# 07-FPGA.net
KiCad netlist of a schematic drawn in Altium Designer
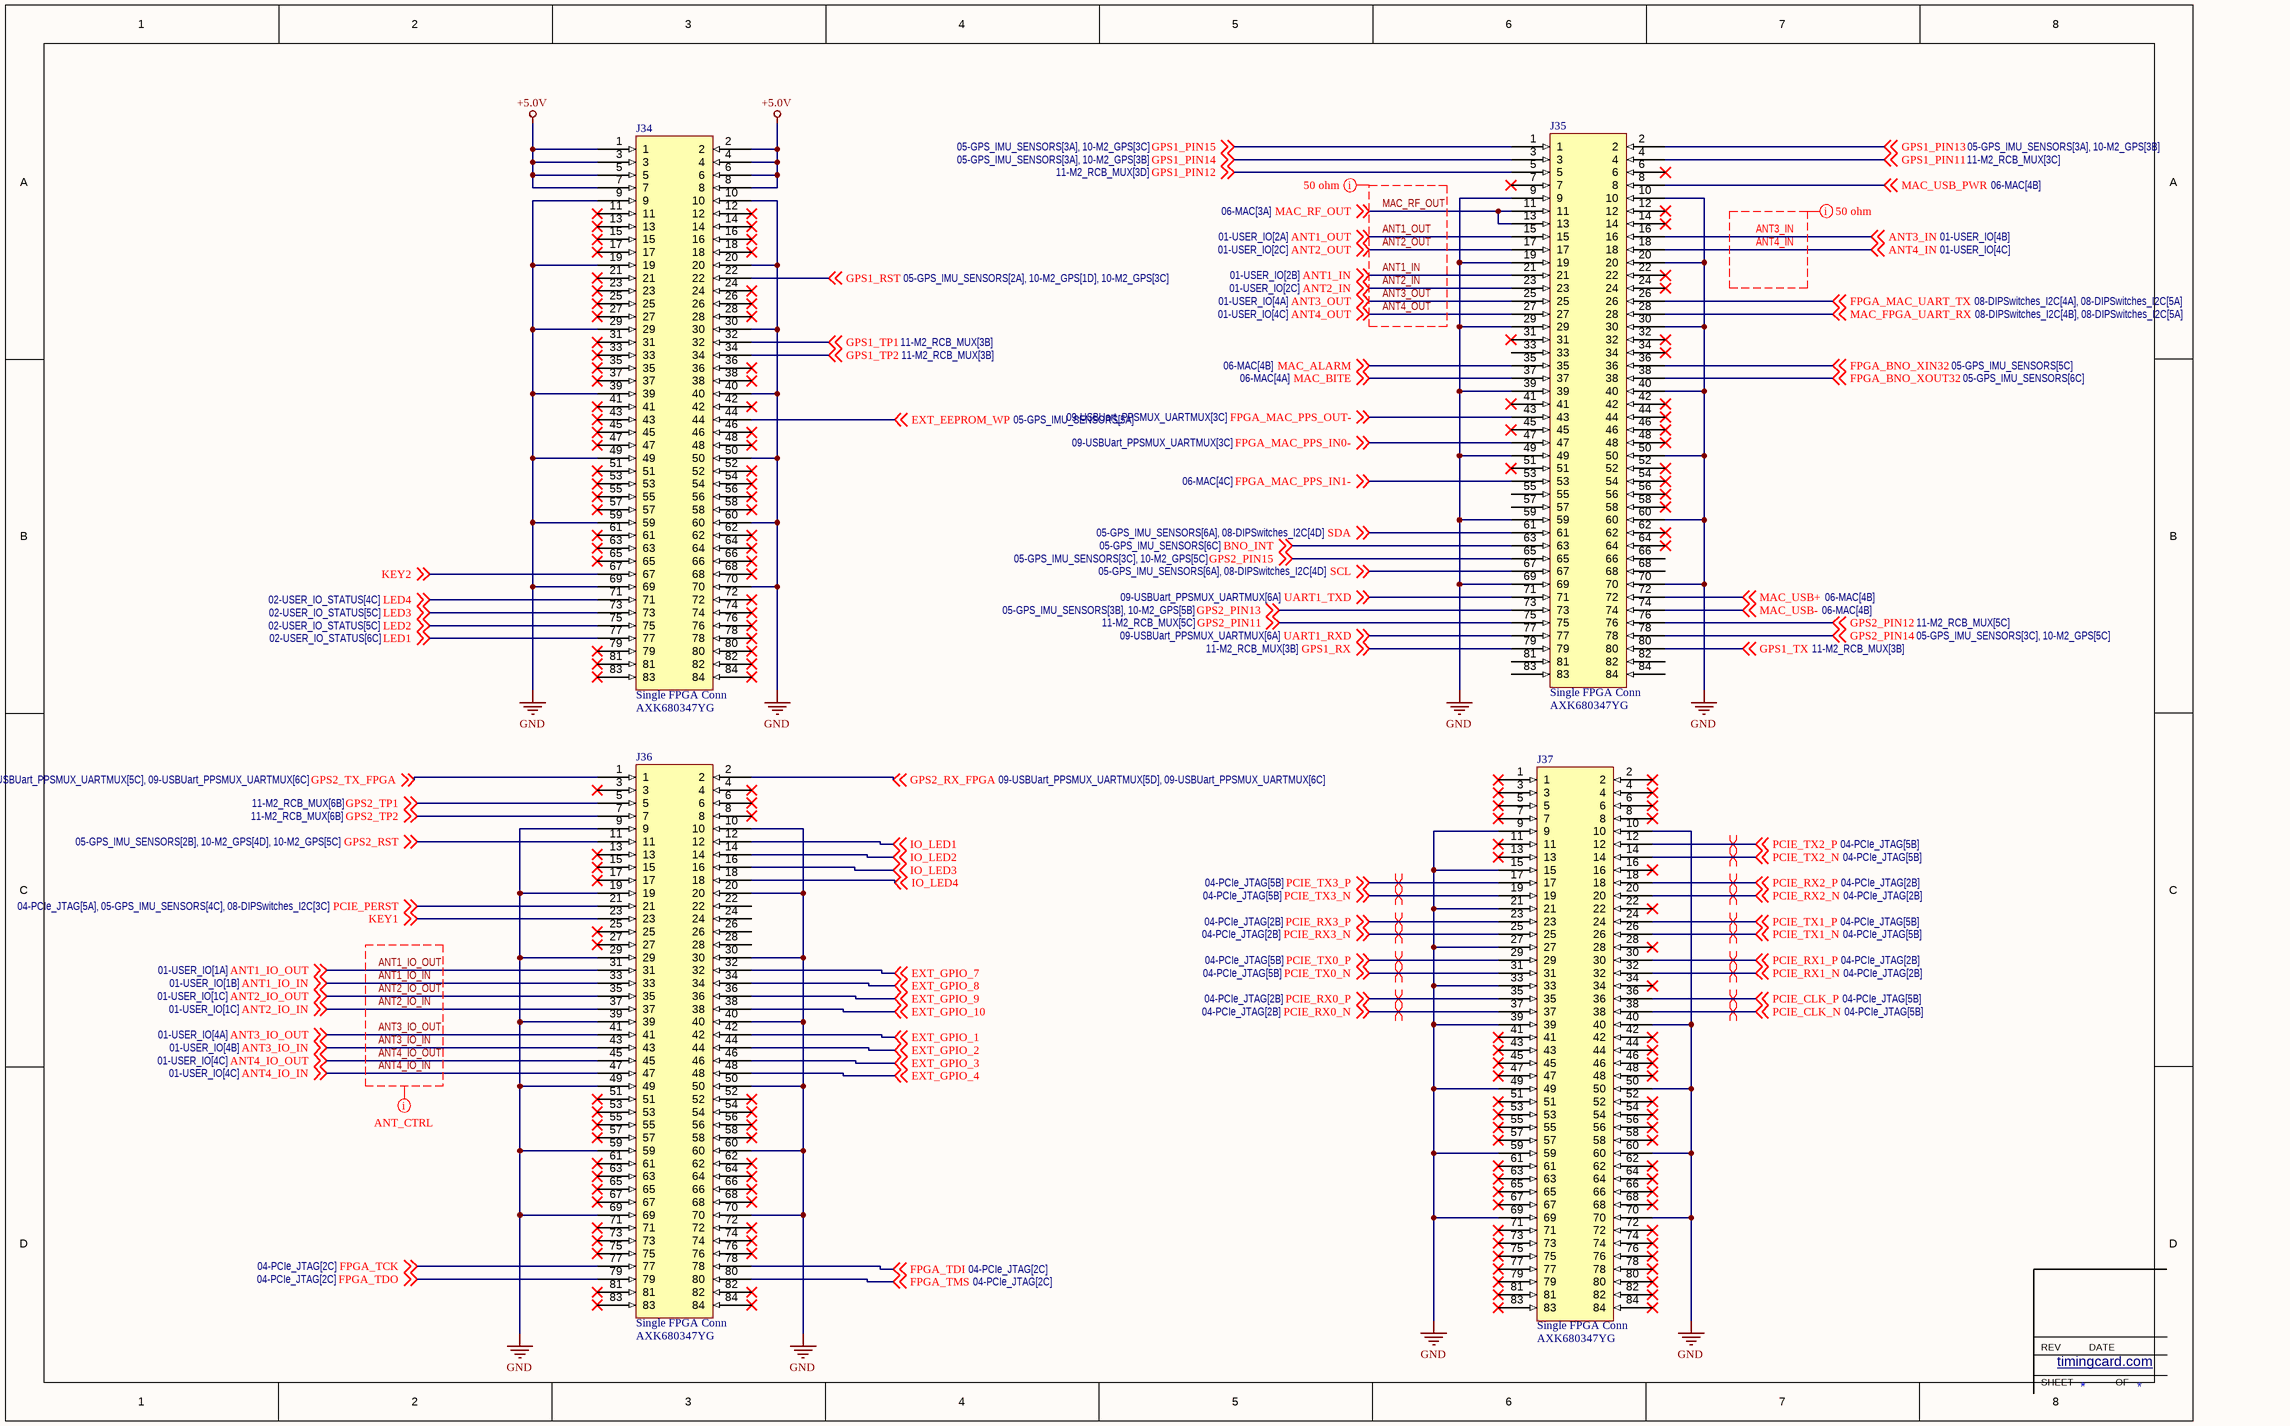
[diagram p0: 07-FPGA.SchDoc]

(export (version "E")
  (design (tool "Eeschema 10.0.6"))
  (components
    (comp (ref "J34")
      (value "Single FPGA Conn")
      (footprint "SingleFPGAConn")
      (description "AXK680347YG")
      (fields (field (name "PART NUMBER") "AXK680347YG"))
      (libsource (lib "FPGA_CONN") (part "Single FPGA Conn"))
    )
    (comp (ref "J35")
      (value "Single FPGA Conn")
      (footprint "SingleFPGAConn")
      (description "AXK680347YG")
      (fields (field (name "PART NUMBER") "AXK680347YG"))
      (libsource (lib "FPGA_CONN") (part "Single FPGA Conn"))
    )
    (comp (ref "J36")
      (value "Single FPGA Conn")
      (footprint "SingleFPGAConn")
      (description "AXK680347YG")
      (fields (field (name "PART NUMBER") "AXK680347YG"))
      (libsource (lib "FPGA_CONN") (part "Single FPGA Conn"))
    )
    (comp (ref "J37")
      (value "Single FPGA Conn")
      (footprint "SingleFPGAConn")
      (description "AXK680347YG")
      (fields (field (name "PART NUMBER") "AXK680347YG"))
      (libsource (lib "FPGA_CONN") (part "Single FPGA Conn"))
    )
  )
  (nets
    (net (code "1") (name "+5.0V") (class "Default")
      (node (ref "J34") (pin "1") (pinfunction "1_1") (pintype "input"))
      (node (ref "J34") (pin "2") (pinfunction "2_2") (pintype "input"))
      (node (ref "J34") (pin "3") (pinfunction "3_3") (pintype "input"))
      (node (ref "J34") (pin "4") (pinfunction "4_4") (pintype "input"))
      (node (ref "J34") (pin "5") (pinfunction "5_5") (pintype "input"))
      (node (ref "J34") (pin "6") (pinfunction "6_6") (pintype "input"))
      (node (ref "J34") (pin "7") (pinfunction "7_7") (pintype "input"))
      (node (ref "J34") (pin "8") (pinfunction "8_8") (pintype "input"))
    )
    (net (code "2") (name "ANT1_IN") (class "Default")
      (node (ref "J35") (pin "21") (pinfunction "21_21") (pintype "input"))
    )
    (net (code "3") (name "ANT1_IO_IN") (class "Default")
      (node (ref "J36") (pin "33") (pinfunction "33_33") (pintype "input"))
    )
    (net (code "4") (name "ANT1_IO_OUT") (class "Default")
      (node (ref "J36") (pin "31") (pinfunction "31_31") (pintype "input"))
    )
    (net (code "5") (name "ANT1_OUT") (class "Default")
      (node (ref "J35") (pin "15") (pinfunction "15_15") (pintype "input"))
    )
    (net (code "6") (name "ANT2_IN") (class "Default")
      (node (ref "J35") (pin "23") (pinfunction "23_23") (pintype "input"))
    )
    (net (code "7") (name "ANT2_IO_IN") (class "Default")
      (node (ref "J36") (pin "37") (pinfunction "37_37") (pintype "input"))
    )
    (net (code "8") (name "ANT2_IO_OUT") (class "Default")
      (node (ref "J36") (pin "35") (pinfunction "35_35") (pintype "input"))
    )
    (net (code "9") (name "ANT2_OUT") (class "Default")
      (node (ref "J35") (pin "17") (pinfunction "17_17") (pintype "input"))
    )
    (net (code "10") (name "ANT3_IN") (class "Default")
      (node (ref "J35") (pin "16") (pinfunction "16_16") (pintype "input"))
    )
    (net (code "11") (name "ANT3_IO_IN") (class "Default")
      (node (ref "J36") (pin "43") (pinfunction "43_43") (pintype "input"))
    )
    (net (code "12") (name "ANT3_IO_OUT") (class "Default")
      (node (ref "J36") (pin "41") (pinfunction "41_41") (pintype "input"))
    )
    (net (code "13") (name "ANT3_OUT") (class "Default")
      (node (ref "J35") (pin "25") (pinfunction "25_25") (pintype "input"))
    )
    (net (code "14") (name "ANT4_IN") (class "Default")
      (node (ref "J35") (pin "18") (pinfunction "18_18") (pintype "input"))
    )
    (net (code "15") (name "ANT4_IO_IN") (class "Default")
      (node (ref "J36") (pin "47") (pinfunction "47_47") (pintype "input"))
    )
    (net (code "16") (name "ANT4_IO_OUT") (class "Default")
      (node (ref "J36") (pin "45") (pinfunction "45_45") (pintype "input"))
    )
    (net (code "17") (name "ANT4_OUT") (class "Default")
      (node (ref "J35") (pin "27") (pinfunction "27_27") (pintype "input"))
    )
    (net (code "18") (name "BNO_INT") (class "Default")
      (node (ref "J35") (pin "63") (pinfunction "63_63") (pintype "input"))
    )
    (net (code "19") (name "EXT_EEPROM_WP") (class "Default")
      (node (ref "J34") (pin "44") (pinfunction "44_44") (pintype "input"))
    )
    (net (code "20") (name "EXT_GPIO_1") (class "Default")
      (node (ref "J36") (pin "42") (pinfunction "42_42") (pintype "input"))
    )
    (net (code "21") (name "EXT_GPIO_2") (class "Default")
      (node (ref "J36") (pin "44") (pinfunction "44_44") (pintype "input"))
    )
    (net (code "22") (name "EXT_GPIO_3") (class "Default")
      (node (ref "J36") (pin "46") (pinfunction "46_46") (pintype "input"))
    )
    (net (code "23") (name "EXT_GPIO_4") (class "Default")
      (node (ref "J36") (pin "48") (pinfunction "48_48") (pintype "input"))
    )
    (net (code "24") (name "EXT_GPIO_7") (class "Default")
      (node (ref "J36") (pin "32") (pinfunction "32_32") (pintype "input"))
    )
    (net (code "25") (name "EXT_GPIO_8") (class "Default")
      (node (ref "J36") (pin "34") (pinfunction "34_34") (pintype "input"))
    )
    (net (code "26") (name "EXT_GPIO_9") (class "Default")
      (node (ref "J36") (pin "36") (pinfunction "36_36") (pintype "input"))
    )
    (net (code "27") (name "EXT_GPIO_10") (class "Default")
      (node (ref "J36") (pin "38") (pinfunction "38_38") (pintype "input"))
    )
    (net (code "28") (name "FPGA_BNO_XIN32") (class "Default")
      (node (ref "J35") (pin "36") (pinfunction "36_36") (pintype "input"))
    )
    (net (code "29") (name "FPGA_BNO_XOUT32") (class "Default")
      (node (ref "J35") (pin "38") (pinfunction "38_38") (pintype "input"))
    )
    (net (code "30") (name "FPGA_MAC_PPS_IN0-") (class "Default")
      (node (ref "J35") (pin "47") (pinfunction "47_47") (pintype "input"))
    )
    (net (code "31") (name "FPGA_MAC_PPS_IN1-") (class "Default")
      (node (ref "J35") (pin "53") (pinfunction "53_53") (pintype "input"))
    )
    (net (code "32") (name "FPGA_MAC_PPS_OUT-") (class "Default")
      (node (ref "J35") (pin "43") (pinfunction "43_43") (pintype "input"))
    )
    (net (code "33") (name "FPGA_MAC_UART_TX") (class "Default")
      (node (ref "J35") (pin "26") (pinfunction "26_26") (pintype "input"))
    )
    (net (code "34") (name "FPGA_TCK") (class "Default")
      (node (ref "J36") (pin "77") (pinfunction "77_77") (pintype "input"))
    )
    (net (code "35") (name "FPGA_TDI") (class "Default")
      (node (ref "J36") (pin "78") (pinfunction "78_78") (pintype "input"))
    )
    (net (code "36") (name "FPGA_TDO") (class "Default")
      (node (ref "J36") (pin "79") (pinfunction "79_79") (pintype "input"))
    )
    (net (code "37") (name "FPGA_TMS") (class "Default")
      (node (ref "J36") (pin "80") (pinfunction "80_80") (pintype "input"))
    )
    (net (code "38") (name "GND") (class "Default")
      (node (ref "J34") (pin "10") (pinfunction "10_10") (pintype "input"))
      (node (ref "J34") (pin "19") (pinfunction "19_19") (pintype "input"))
      (node (ref "J34") (pin "20") (pinfunction "20_20") (pintype "input"))
      (node (ref "J34") (pin "29") (pinfunction "29_29") (pintype "input"))
      (node (ref "J34") (pin "30") (pinfunction "30_30") (pintype "input"))
      (node (ref "J34") (pin "39") (pinfunction "39_39") (pintype "input"))
      (node (ref "J34") (pin "40") (pinfunction "40_40") (pintype "input"))
      (node (ref "J34") (pin "49") (pinfunction "49_49") (pintype "input"))
      (node (ref "J34") (pin "50") (pinfunction "50_50") (pintype "input"))
      (node (ref "J34") (pin "59") (pinfunction "59_59") (pintype "input"))
      (node (ref "J34") (pin "60") (pinfunction "60_60") (pintype "input"))
      (node (ref "J34") (pin "69") (pinfunction "69_69") (pintype "input"))
      (node (ref "J34") (pin "70") (pinfunction "70_70") (pintype "input"))
      (node (ref "J34") (pin "9") (pinfunction "9_9") (pintype "input"))
      (node (ref "J35") (pin "10") (pinfunction "10_10") (pintype "input"))
      (node (ref "J35") (pin "19") (pinfunction "19_19") (pintype "input"))
      (node (ref "J35") (pin "20") (pinfunction "20_20") (pintype "input"))
      (node (ref "J35") (pin "29") (pinfunction "29_29") (pintype "input"))
      (node (ref "J35") (pin "30") (pinfunction "30_30") (pintype "input"))
      (node (ref "J35") (pin "39") (pinfunction "39_39") (pintype "input"))
      (node (ref "J35") (pin "40") (pinfunction "40_40") (pintype "input"))
      (node (ref "J35") (pin "49") (pinfunction "49_49") (pintype "input"))
      (node (ref "J35") (pin "50") (pinfunction "50_50") (pintype "input"))
      (node (ref "J35") (pin "59") (pinfunction "59_59") (pintype "input"))
      (node (ref "J35") (pin "60") (pinfunction "60_60") (pintype "input"))
      (node (ref "J35") (pin "69") (pinfunction "69_69") (pintype "input"))
      (node (ref "J35") (pin "70") (pinfunction "70_70") (pintype "input"))
      (node (ref "J35") (pin "9") (pinfunction "9_9") (pintype "input"))
      (node (ref "J36") (pin "10") (pinfunction "10_10") (pintype "input"))
      (node (ref "J36") (pin "19") (pinfunction "19_19") (pintype "input"))
      (node (ref "J36") (pin "20") (pinfunction "20_20") (pintype "input"))
      (node (ref "J36") (pin "29") (pinfunction "29_29") (pintype "input"))
      (node (ref "J36") (pin "30") (pinfunction "30_30") (pintype "input"))
      (node (ref "J36") (pin "39") (pinfunction "39_39") (pintype "input"))
      (node (ref "J36") (pin "40") (pinfunction "40_40") (pintype "input"))
      (node (ref "J36") (pin "49") (pinfunction "49_49") (pintype "input"))
      (node (ref "J36") (pin "50") (pinfunction "50_50") (pintype "input"))
      (node (ref "J36") (pin "59") (pinfunction "59_59") (pintype "input"))
      (node (ref "J36") (pin "60") (pinfunction "60_60") (pintype "input"))
      (node (ref "J36") (pin "69") (pinfunction "69_69") (pintype "input"))
      (node (ref "J36") (pin "70") (pinfunction "70_70") (pintype "input"))
      (node (ref "J36") (pin "9") (pinfunction "9_9") (pintype "input"))
      (node (ref "J37") (pin "10") (pinfunction "10_10") (pintype "input"))
      (node (ref "J37") (pin "15") (pinfunction "15_15") (pintype "input"))
      (node (ref "J37") (pin "21") (pinfunction "21_21") (pintype "input"))
      (node (ref "J37") (pin "27") (pinfunction "27_27") (pintype "input"))
      (node (ref "J37") (pin "33") (pinfunction "33_33") (pintype "input"))
      (node (ref "J37") (pin "39") (pinfunction "39_39") (pintype "input"))
      (node (ref "J37") (pin "40") (pinfunction "40_40") (pintype "input"))
      (node (ref "J37") (pin "49") (pinfunction "49_49") (pintype "input"))
      (node (ref "J37") (pin "50") (pinfunction "50_50") (pintype "input"))
      (node (ref "J37") (pin "59") (pinfunction "59_59") (pintype "input"))
      (node (ref "J37") (pin "60") (pinfunction "60_60") (pintype "input"))
      (node (ref "J37") (pin "69") (pinfunction "69_69") (pintype "input"))
      (node (ref "J37") (pin "70") (pinfunction "70_70") (pintype "input"))
      (node (ref "J37") (pin "9") (pinfunction "9_9") (pintype "input"))
    )
    (net (code "39") (name "GPS1_PIN11") (class "Default")
      (node (ref "J35") (pin "4") (pinfunction "4_4") (pintype "input"))
    )
    (net (code "40") (name "GPS1_PIN12") (class "Default")
      (node (ref "J35") (pin "5") (pinfunction "5_5") (pintype "input"))
    )
    (net (code "41") (name "GPS1_PIN13") (class "Default")
      (node (ref "J35") (pin "2") (pinfunction "2_2") (pintype "input"))
    )
    (net (code "42") (name "GPS1_PIN14") (class "Default")
      (node (ref "J35") (pin "3") (pinfunction "3_3") (pintype "input"))
    )
    (net (code "43") (name "GPS1_PIN15") (class "Default")
      (node (ref "J35") (pin "1") (pinfunction "1_1") (pintype "input"))
    )
    (net (code "44") (name "GPS1_RST") (class "Default")
      (node (ref "J34") (pin "22") (pinfunction "22_22") (pintype "input"))
    )
    (net (code "45") (name "GPS1_RX") (class "Default")
      (node (ref "J35") (pin "79") (pinfunction "79_79") (pintype "input"))
    )
    (net (code "46") (name "GPS1_TP1") (class "Default")
      (node (ref "J34") (pin "32") (pinfunction "32_32") (pintype "input"))
    )
    (net (code "47") (name "GPS1_TP2") (class "Default")
      (node (ref "J34") (pin "34") (pinfunction "34_34") (pintype "input"))
    )
    (net (code "48") (name "GPS1_TX") (class "Default")
      (node (ref "J35") (pin "80") (pinfunction "80_80") (pintype "input"))
    )
    (net (code "49") (name "GPS2_PIN11") (class "Default")
      (node (ref "J35") (pin "75") (pinfunction "75_75") (pintype "input"))
    )
    (net (code "50") (name "GPS2_PIN12") (class "Default")
      (node (ref "J35") (pin "76") (pinfunction "76_76") (pintype "input"))
    )
    (net (code "51") (name "GPS2_PIN13") (class "Default")
      (node (ref "J35") (pin "73") (pinfunction "73_73") (pintype "input"))
    )
    (net (code "52") (name "GPS2_PIN14") (class "Default")
      (node (ref "J35") (pin "78") (pinfunction "78_78") (pintype "input"))
    )
    (net (code "53") (name "GPS2_PIN15") (class "Default")
      (node (ref "J35") (pin "65") (pinfunction "65_65") (pintype "input"))
    )
    (net (code "54") (name "GPS2_RST") (class "Default")
      (node (ref "J36") (pin "11") (pinfunction "11_11") (pintype "input"))
    )
    (net (code "55") (name "GPS2_RX_FPGA") (class "Default")
      (node (ref "J36") (pin "2") (pinfunction "2_2") (pintype "input"))
    )
    (net (code "56") (name "GPS2_TP1") (class "Default")
      (node (ref "J36") (pin "5") (pinfunction "5_5") (pintype "input"))
    )
    (net (code "57") (name "GPS2_TP2") (class "Default")
      (node (ref "J36") (pin "7") (pinfunction "7_7") (pintype "input"))
    )
    (net (code "58") (name "GPS2_TX_FPGA") (class "Default")
      (node (ref "J36") (pin "1") (pinfunction "1_1") (pintype "input"))
    )
    (net (code "59") (name "IO_LED1") (class "Default")
      (node (ref "J36") (pin "12") (pinfunction "12_12") (pintype "input"))
    )
    (net (code "60") (name "IO_LED2") (class "Default")
      (node (ref "J36") (pin "14") (pinfunction "14_14") (pintype "input"))
    )
    (net (code "61") (name "IO_LED3") (class "Default")
      (node (ref "J36") (pin "16") (pinfunction "16_16") (pintype "input"))
    )
    (net (code "62") (name "IO_LED4") (class "Default")
      (node (ref "J36") (pin "18") (pinfunction "18_18") (pintype "input"))
    )
    (net (code "63") (name "KEY1") (class "Default")
      (node (ref "J36") (pin "23") (pinfunction "23_23") (pintype "input"))
    )
    (net (code "64") (name "KEY2") (class "Default")
      (node (ref "J34") (pin "67") (pinfunction "67_67") (pintype "input"))
    )
    (net (code "65") (name "LED1") (class "Default")
      (node (ref "J34") (pin "77") (pinfunction "77_77") (pintype "input"))
    )
    (net (code "66") (name "LED2") (class "Default")
      (node (ref "J34") (pin "75") (pinfunction "75_75") (pintype "input"))
    )
    (net (code "67") (name "LED3") (class "Default")
      (node (ref "J34") (pin "73") (pinfunction "73_73") (pintype "input"))
    )
    (net (code "68") (name "LED4") (class "Default")
      (node (ref "J34") (pin "71") (pinfunction "71_71") (pintype "input"))
    )
    (net (code "69") (name "MAC_ALARM") (class "Default")
      (node (ref "J35") (pin "35") (pinfunction "35_35") (pintype "input"))
    )
    (net (code "70") (name "MAC_BITE") (class "Default")
      (node (ref "J35") (pin "37") (pinfunction "37_37") (pintype "input"))
    )
    (net (code "71") (name "MAC_FPGA_UART_RX") (class "Default")
      (node (ref "J35") (pin "28") (pinfunction "28_28") (pintype "input"))
    )
    (net (code "72") (name "MAC_RF_OUT") (class "Default")
      (node (ref "J35") (pin "11") (pinfunction "11_11") (pintype "input"))
      (node (ref "J35") (pin "13") (pinfunction "13_13") (pintype "input"))
    )
    (net (code "73") (name "MAC_USB+") (class "Default")
      (node (ref "J35") (pin "72") (pinfunction "72_72") (pintype "input"))
    )
    (net (code "74") (name "MAC_USB-") (class "Default")
      (node (ref "J35") (pin "74") (pinfunction "74_74") (pintype "input"))
    )
    (net (code "75") (name "MAC_USB_PWR") (class "Default")
      (node (ref "J35") (pin "8") (pinfunction "8_8") (pintype "input"))
    )
    (net (code "76") (name "PCIE_CLK_N") (class "Default")
      (node (ref "J37") (pin "38") (pinfunction "38_38") (pintype "input"))
    )
    (net (code "77") (name "PCIE_CLK_P") (class "Default")
      (node (ref "J37") (pin "36") (pinfunction "36_36") (pintype "input"))
    )
    (net (code "78") (name "PCIE_PERST") (class "Default")
      (node (ref "J36") (pin "21") (pinfunction "21_21") (pintype "input"))
    )
    (net (code "79") (name "PCIE_RX0_N") (class "Default")
      (node (ref "J37") (pin "37") (pinfunction "37_37") (pintype "input"))
    )
    (net (code "80") (name "PCIE_RX0_P") (class "Default")
      (node (ref "J37") (pin "35") (pinfunction "35_35") (pintype "input"))
    )
    (net (code "81") (name "PCIE_RX1_N") (class "Default")
      (node (ref "J37") (pin "32") (pinfunction "32_32") (pintype "input"))
    )
    (net (code "82") (name "PCIE_RX1_P") (class "Default")
      (node (ref "J37") (pin "30") (pinfunction "30_30") (pintype "input"))
    )
    (net (code "83") (name "PCIE_RX2_N") (class "Default")
      (node (ref "J37") (pin "20") (pinfunction "20_20") (pintype "input"))
    )
    (net (code "84") (name "PCIE_RX2_P") (class "Default")
      (node (ref "J37") (pin "18") (pinfunction "18_18") (pintype "input"))
    )
    (net (code "85") (name "PCIE_RX3_N") (class "Default")
      (node (ref "J37") (pin "25") (pinfunction "25_25") (pintype "input"))
    )
    (net (code "86") (name "PCIE_RX3_P") (class "Default")
      (node (ref "J37") (pin "23") (pinfunction "23_23") (pintype "input"))
    )
    (net (code "87") (name "PCIE_TX0_N") (class "Default")
      (node (ref "J37") (pin "31") (pinfunction "31_31") (pintype "input"))
    )
    (net (code "88") (name "PCIE_TX0_P") (class "Default")
      (node (ref "J37") (pin "29") (pinfunction "29_29") (pintype "input"))
    )
    (net (code "89") (name "PCIE_TX1_N") (class "Default")
      (node (ref "J37") (pin "26") (pinfunction "26_26") (pintype "input"))
    )
    (net (code "90") (name "PCIE_TX1_P") (class "Default")
      (node (ref "J37") (pin "24") (pinfunction "24_24") (pintype "input"))
    )
    (net (code "91") (name "PCIE_TX2_N") (class "Default")
      (node (ref "J37") (pin "14") (pinfunction "14_14") (pintype "input"))
    )
    (net (code "92") (name "PCIE_TX2_P") (class "Default")
      (node (ref "J37") (pin "12") (pinfunction "12_12") (pintype "input"))
    )
    (net (code "93") (name "PCIE_TX3_N") (class "Default")
      (node (ref "J37") (pin "19") (pinfunction "19_19") (pintype "input"))
    )
    (net (code "94") (name "PCIE_TX3_P") (class "Default")
      (node (ref "J37") (pin "17") (pinfunction "17_17") (pintype "input"))
    )
    (net (code "95") (name "SCL") (class "Default")
      (node (ref "J35") (pin "67") (pinfunction "67_67") (pintype "input"))
    )
    (net (code "96") (name "SDA") (class "Default")
      (node (ref "J35") (pin "61") (pinfunction "61_61") (pintype "input"))
    )
    (net (code "97") (name "UART1_RXD") (class "Default")
      (node (ref "J35") (pin "77") (pinfunction "77_77") (pintype "input"))
    )
    (net (code "98") (name "UART1_TXD") (class "Default")
      (node (ref "J35") (pin "71") (pinfunction "71_71") (pintype "input"))
    )
    (net (code "99") (name "unconnected-(J34-Pad11)") (class "Default")
      (node (ref "J34") (pin "11") (pinfunction "11_11") (pintype "input+no_connect"))
    )
    (net (code "100") (name "unconnected-(J34-Pad12)") (class "Default")
      (node (ref "J34") (pin "12") (pinfunction "12_12") (pintype "input+no_connect"))
    )
    (net (code "101") (name "unconnected-(J34-Pad13)") (class "Default")
      (node (ref "J34") (pin "13") (pinfunction "13_13") (pintype "input+no_connect"))
    )
    (net (code "102") (name "unconnected-(J34-Pad14)") (class "Default")
      (node (ref "J34") (pin "14") (pinfunction "14_14") (pintype "input+no_connect"))
    )
    (net (code "103") (name "unconnected-(J34-Pad15)") (class "Default")
      (node (ref "J34") (pin "15") (pinfunction "15_15") (pintype "input+no_connect"))
    )
    (net (code "104") (name "unconnected-(J34-Pad16)") (class "Default")
      (node (ref "J34") (pin "16") (pinfunction "16_16") (pintype "input+no_connect"))
    )
    (net (code "105") (name "unconnected-(J34-Pad17)") (class "Default")
      (node (ref "J34") (pin "17") (pinfunction "17_17") (pintype "input+no_connect"))
    )
    (net (code "106") (name "unconnected-(J34-Pad18)") (class "Default")
      (node (ref "J34") (pin "18") (pinfunction "18_18") (pintype "input+no_connect"))
    )
    (net (code "107") (name "unconnected-(J34-Pad21)") (class "Default")
      (node (ref "J34") (pin "21") (pinfunction "21_21") (pintype "input+no_connect"))
    )
    (net (code "108") (name "unconnected-(J34-Pad23)") (class "Default")
      (node (ref "J34") (pin "23") (pinfunction "23_23") (pintype "input+no_connect"))
    )
    (net (code "109") (name "unconnected-(J34-Pad24)") (class "Default")
      (node (ref "J34") (pin "24") (pinfunction "24_24") (pintype "input+no_connect"))
    )
    (net (code "110") (name "unconnected-(J34-Pad25)") (class "Default")
      (node (ref "J34") (pin "25") (pinfunction "25_25") (pintype "input+no_connect"))
    )
    (net (code "111") (name "unconnected-(J34-Pad26)") (class "Default")
      (node (ref "J34") (pin "26") (pinfunction "26_26") (pintype "input+no_connect"))
    )
    (net (code "112") (name "unconnected-(J34-Pad27)") (class "Default")
      (node (ref "J34") (pin "27") (pinfunction "27_27") (pintype "input+no_connect"))
    )
    (net (code "113") (name "unconnected-(J34-Pad28)") (class "Default")
      (node (ref "J34") (pin "28") (pinfunction "28_28") (pintype "input+no_connect"))
    )
    (net (code "114") (name "unconnected-(J34-Pad31)") (class "Default")
      (node (ref "J34") (pin "31") (pinfunction "31_31") (pintype "input+no_connect"))
    )
    (net (code "115") (name "unconnected-(J34-Pad33)") (class "Default")
      (node (ref "J34") (pin "33") (pinfunction "33_33") (pintype "input+no_connect"))
    )
    (net (code "116") (name "unconnected-(J34-Pad35)") (class "Default")
      (node (ref "J34") (pin "35") (pinfunction "35_35") (pintype "input+no_connect"))
    )
    (net (code "117") (name "unconnected-(J34-Pad36)") (class "Default")
      (node (ref "J34") (pin "36") (pinfunction "36_36") (pintype "input+no_connect"))
    )
    (net (code "118") (name "unconnected-(J34-Pad37)") (class "Default")
      (node (ref "J34") (pin "37") (pinfunction "37_37") (pintype "input+no_connect"))
    )
    (net (code "119") (name "unconnected-(J34-Pad38)") (class "Default")
      (node (ref "J34") (pin "38") (pinfunction "38_38") (pintype "input+no_connect"))
    )
    (net (code "120") (name "unconnected-(J34-Pad41)") (class "Default")
      (node (ref "J34") (pin "41") (pinfunction "41_41") (pintype "input+no_connect"))
    )
    (net (code "121") (name "unconnected-(J34-Pad42)") (class "Default")
      (node (ref "J34") (pin "42") (pinfunction "42_42") (pintype "input+no_connect"))
    )
    (net (code "122") (name "unconnected-(J34-Pad43)") (class "Default")
      (node (ref "J34") (pin "43") (pinfunction "43_43") (pintype "input+no_connect"))
    )
    (net (code "123") (name "unconnected-(J34-Pad45)") (class "Default")
      (node (ref "J34") (pin "45") (pinfunction "45_45") (pintype "input+no_connect"))
    )
    (net (code "124") (name "unconnected-(J34-Pad46)") (class "Default")
      (node (ref "J34") (pin "46") (pinfunction "46_46") (pintype "input+no_connect"))
    )
    (net (code "125") (name "unconnected-(J34-Pad47)") (class "Default")
      (node (ref "J34") (pin "47") (pinfunction "47_47") (pintype "input+no_connect"))
    )
    (net (code "126") (name "unconnected-(J34-Pad48)") (class "Default")
      (node (ref "J34") (pin "48") (pinfunction "48_48") (pintype "input+no_connect"))
    )
    (net (code "127") (name "unconnected-(J34-Pad51)") (class "Default")
      (node (ref "J34") (pin "51") (pinfunction "51_51") (pintype "input+no_connect"))
    )
    (net (code "128") (name "unconnected-(J34-Pad52)") (class "Default")
      (node (ref "J34") (pin "52") (pinfunction "52_52") (pintype "input+no_connect"))
    )
    (net (code "129") (name "unconnected-(J34-Pad53)") (class "Default")
      (node (ref "J34") (pin "53") (pinfunction "53_53") (pintype "input+no_connect"))
    )
    (net (code "130") (name "unconnected-(J34-Pad54)") (class "Default")
      (node (ref "J34") (pin "54") (pinfunction "54_54") (pintype "input+no_connect"))
    )
    (net (code "131") (name "unconnected-(J34-Pad55)") (class "Default")
      (node (ref "J34") (pin "55") (pinfunction "55_55") (pintype "input+no_connect"))
    )
    (net (code "132") (name "unconnected-(J34-Pad56)") (class "Default")
      (node (ref "J34") (pin "56") (pinfunction "56_56") (pintype "input+no_connect"))
    )
    (net (code "133") (name "unconnected-(J34-Pad57)") (class "Default")
      (node (ref "J34") (pin "57") (pinfunction "57_57") (pintype "input+no_connect"))
    )
    (net (code "134") (name "unconnected-(J34-Pad58)") (class "Default")
      (node (ref "J34") (pin "58") (pinfunction "58_58") (pintype "input+no_connect"))
    )
    (net (code "135") (name "unconnected-(J34-Pad61)") (class "Default")
      (node (ref "J34") (pin "61") (pinfunction "61_61") (pintype "input+no_connect"))
    )
    (net (code "136") (name "unconnected-(J34-Pad62)") (class "Default")
      (node (ref "J34") (pin "62") (pinfunction "62_62") (pintype "input+no_connect"))
    )
    (net (code "137") (name "unconnected-(J34-Pad63)") (class "Default")
      (node (ref "J34") (pin "63") (pinfunction "63_63") (pintype "input+no_connect"))
    )
    (net (code "138") (name "unconnected-(J34-Pad64)") (class "Default")
      (node (ref "J34") (pin "64") (pinfunction "64_64") (pintype "input+no_connect"))
    )
    (net (code "139") (name "unconnected-(J34-Pad65)") (class "Default")
      (node (ref "J34") (pin "65") (pinfunction "65_65") (pintype "input+no_connect"))
    )
    (net (code "140") (name "unconnected-(J34-Pad66)") (class "Default")
      (node (ref "J34") (pin "66") (pinfunction "66_66") (pintype "input+no_connect"))
    )
    (net (code "141") (name "unconnected-(J34-Pad68)") (class "Default")
      (node (ref "J34") (pin "68") (pinfunction "68_68") (pintype "input+no_connect"))
    )
    (net (code "142") (name "unconnected-(J34-Pad72)") (class "Default")
      (node (ref "J34") (pin "72") (pinfunction "72_72") (pintype "input+no_connect"))
    )
    (net (code "143") (name "unconnected-(J34-Pad74)") (class "Default")
      (node (ref "J34") (pin "74") (pinfunction "74_74") (pintype "input+no_connect"))
    )
    (net (code "144") (name "unconnected-(J34-Pad76)") (class "Default")
      (node (ref "J34") (pin "76") (pinfunction "76_76") (pintype "input+no_connect"))
    )
    (net (code "145") (name "unconnected-(J34-Pad78)") (class "Default")
      (node (ref "J34") (pin "78") (pinfunction "78_78") (pintype "input+no_connect"))
    )
    (net (code "146") (name "unconnected-(J34-Pad79)") (class "Default")
      (node (ref "J34") (pin "79") (pinfunction "79_79") (pintype "input+no_connect"))
    )
    (net (code "147") (name "unconnected-(J34-Pad80)") (class "Default")
      (node (ref "J34") (pin "80") (pinfunction "80_80") (pintype "input+no_connect"))
    )
    (net (code "148") (name "unconnected-(J34-Pad81)") (class "Default")
      (node (ref "J34") (pin "81") (pinfunction "81_81") (pintype "input+no_connect"))
    )
    (net (code "149") (name "unconnected-(J34-Pad82)") (class "Default")
      (node (ref "J34") (pin "82") (pinfunction "82_82") (pintype "input+no_connect"))
    )
    (net (code "150") (name "unconnected-(J34-Pad83)") (class "Default")
      (node (ref "J34") (pin "83") (pinfunction "83_83") (pintype "input+no_connect"))
    )
    (net (code "151") (name "unconnected-(J34-Pad84)") (class "Default")
      (node (ref "J34") (pin "84") (pinfunction "84_84") (pintype "input+no_connect"))
    )
    (net (code "152") (name "unconnected-(J35-Pad6)") (class "Default")
      (node (ref "J35") (pin "6") (pinfunction "6_6") (pintype "input+no_connect"))
    )
    (net (code "153") (name "unconnected-(J35-Pad7)") (class "Default")
      (node (ref "J35") (pin "7") (pinfunction "7_7") (pintype "input+no_connect"))
    )
    (net (code "154") (name "unconnected-(J35-Pad12)") (class "Default")
      (node (ref "J35") (pin "12") (pinfunction "12_12") (pintype "input+no_connect"))
    )
    (net (code "155") (name "unconnected-(J35-Pad14)") (class "Default")
      (node (ref "J35") (pin "14") (pinfunction "14_14") (pintype "input+no_connect"))
    )
    (net (code "156") (name "unconnected-(J35-Pad22)") (class "Default")
      (node (ref "J35") (pin "22") (pinfunction "22_22") (pintype "input+no_connect"))
    )
    (net (code "157") (name "unconnected-(J35-Pad24)") (class "Default")
      (node (ref "J35") (pin "24") (pinfunction "24_24") (pintype "input+no_connect"))
    )
    (net (code "158") (name "unconnected-(J35-Pad31)") (class "Default")
      (node (ref "J35") (pin "31") (pinfunction "31_31") (pintype "input+no_connect"))
    )
    (net (code "159") (name "unconnected-(J35-Pad32)") (class "Default")
      (node (ref "J35") (pin "32") (pinfunction "32_32") (pintype "input+no_connect"))
    )
    (net (code "160") (name "unconnected-(J35-Pad33)") (class "Default")
      (node (ref "J35") (pin "33") (pinfunction "33_33") (pintype "input"))
    )
    (net (code "161") (name "unconnected-(J35-Pad34)") (class "Default")
      (node (ref "J35") (pin "34") (pinfunction "34_34") (pintype "input+no_connect"))
    )
    (net (code "162") (name "unconnected-(J35-Pad41)") (class "Default")
      (node (ref "J35") (pin "41") (pinfunction "41_41") (pintype "input+no_connect"))
    )
    (net (code "163") (name "unconnected-(J35-Pad42)") (class "Default")
      (node (ref "J35") (pin "42") (pinfunction "42_42") (pintype "input+no_connect"))
    )
    (net (code "164") (name "unconnected-(J35-Pad44)") (class "Default")
      (node (ref "J35") (pin "44") (pinfunction "44_44") (pintype "input+no_connect"))
    )
    (net (code "165") (name "unconnected-(J35-Pad45)") (class "Default")
      (node (ref "J35") (pin "45") (pinfunction "45_45") (pintype "input+no_connect"))
    )
    (net (code "166") (name "unconnected-(J35-Pad46)") (class "Default")
      (node (ref "J35") (pin "46") (pinfunction "46_46") (pintype "input+no_connect"))
    )
    (net (code "167") (name "unconnected-(J35-Pad48)") (class "Default")
      (node (ref "J35") (pin "48") (pinfunction "48_48") (pintype "input+no_connect"))
    )
    (net (code "168") (name "unconnected-(J35-Pad51)") (class "Default")
      (node (ref "J35") (pin "51") (pinfunction "51_51") (pintype "input+no_connect"))
    )
    (net (code "169") (name "unconnected-(J35-Pad52)") (class "Default")
      (node (ref "J35") (pin "52") (pinfunction "52_52") (pintype "input+no_connect"))
    )
    (net (code "170") (name "unconnected-(J35-Pad54)") (class "Default")
      (node (ref "J35") (pin "54") (pinfunction "54_54") (pintype "input+no_connect"))
    )
    (net (code "171") (name "unconnected-(J35-Pad55)") (class "Default")
      (node (ref "J35") (pin "55") (pinfunction "55_55") (pintype "input"))
    )
    (net (code "172") (name "unconnected-(J35-Pad56)") (class "Default")
      (node (ref "J35") (pin "56") (pinfunction "56_56") (pintype "input+no_connect"))
    )
    (net (code "173") (name "unconnected-(J35-Pad57)") (class "Default")
      (node (ref "J35") (pin "57") (pinfunction "57_57") (pintype "input"))
    )
    (net (code "174") (name "unconnected-(J35-Pad58)") (class "Default")
      (node (ref "J35") (pin "58") (pinfunction "58_58") (pintype "input+no_connect"))
    )
    (net (code "175") (name "unconnected-(J35-Pad62)") (class "Default")
      (node (ref "J35") (pin "62") (pinfunction "62_62") (pintype "input+no_connect"))
    )
    (net (code "176") (name "unconnected-(J35-Pad64)") (class "Default")
      (node (ref "J35") (pin "64") (pinfunction "64_64") (pintype "input+no_connect"))
    )
    (net (code "177") (name "unconnected-(J35-Pad66)") (class "Default")
      (node (ref "J35") (pin "66") (pinfunction "66_66") (pintype "input"))
    )
    (net (code "178") (name "unconnected-(J35-Pad68)") (class "Default")
      (node (ref "J35") (pin "68") (pinfunction "68_68") (pintype "input"))
    )
    (net (code "179") (name "unconnected-(J35-Pad81)") (class "Default")
      (node (ref "J35") (pin "81") (pinfunction "81_81") (pintype "input"))
    )
    (net (code "180") (name "unconnected-(J35-Pad82)") (class "Default")
      (node (ref "J35") (pin "82") (pinfunction "82_82") (pintype "input"))
    )
    (net (code "181") (name "unconnected-(J35-Pad83)") (class "Default")
      (node (ref "J35") (pin "83") (pinfunction "83_83") (pintype "input"))
    )
    (net (code "182") (name "unconnected-(J35-Pad84)") (class "Default")
      (node (ref "J35") (pin "84") (pinfunction "84_84") (pintype "input"))
    )
    (net (code "183") (name "unconnected-(J36-Pad3)") (class "Default")
      (node (ref "J36") (pin "3") (pinfunction "3_3") (pintype "input+no_connect"))
    )
    (net (code "184") (name "unconnected-(J36-Pad4)") (class "Default")
      (node (ref "J36") (pin "4") (pinfunction "4_4") (pintype "input+no_connect"))
    )
    (net (code "185") (name "unconnected-(J36-Pad6)") (class "Default")
      (node (ref "J36") (pin "6") (pinfunction "6_6") (pintype "input+no_connect"))
    )
    (net (code "186") (name "unconnected-(J36-Pad8)") (class "Default")
      (node (ref "J36") (pin "8") (pinfunction "8_8") (pintype "input+no_connect"))
    )
    (net (code "187") (name "unconnected-(J36-Pad13)") (class "Default")
      (node (ref "J36") (pin "13") (pinfunction "13_13") (pintype "input+no_connect"))
    )
    (net (code "188") (name "unconnected-(J36-Pad15)") (class "Default")
      (node (ref "J36") (pin "15") (pinfunction "15_15") (pintype "input+no_connect"))
    )
    (net (code "189") (name "unconnected-(J36-Pad17)") (class "Default")
      (node (ref "J36") (pin "17") (pinfunction "17_17") (pintype "input+no_connect"))
    )
    (net (code "190") (name "unconnected-(J36-Pad22)") (class "Default")
      (node (ref "J36") (pin "22") (pinfunction "22_22") (pintype "input"))
    )
    (net (code "191") (name "unconnected-(J36-Pad24)") (class "Default")
      (node (ref "J36") (pin "24") (pinfunction "24_24") (pintype "input"))
    )
    (net (code "192") (name "unconnected-(J36-Pad25)") (class "Default")
      (node (ref "J36") (pin "25") (pinfunction "25_25") (pintype "input+no_connect"))
    )
    (net (code "193") (name "unconnected-(J36-Pad26)") (class "Default")
      (node (ref "J36") (pin "26") (pinfunction "26_26") (pintype "input"))
    )
    (net (code "194") (name "unconnected-(J36-Pad27)") (class "Default")
      (node (ref "J36") (pin "27") (pinfunction "27_27") (pintype "input+no_connect"))
    )
    (net (code "195") (name "unconnected-(J36-Pad28)") (class "Default")
      (node (ref "J36") (pin "28") (pinfunction "28_28") (pintype "input"))
    )
    (net (code "196") (name "unconnected-(J36-Pad51)") (class "Default")
      (node (ref "J36") (pin "51") (pinfunction "51_51") (pintype "input+no_connect"))
    )
    (net (code "197") (name "unconnected-(J36-Pad52)") (class "Default")
      (node (ref "J36") (pin "52") (pinfunction "52_52") (pintype "input+no_connect"))
    )
    (net (code "198") (name "unconnected-(J36-Pad53)") (class "Default")
      (node (ref "J36") (pin "53") (pinfunction "53_53") (pintype "input+no_connect"))
    )
    (net (code "199") (name "unconnected-(J36-Pad54)") (class "Default")
      (node (ref "J36") (pin "54") (pinfunction "54_54") (pintype "input+no_connect"))
    )
    (net (code "200") (name "unconnected-(J36-Pad55)") (class "Default")
      (node (ref "J36") (pin "55") (pinfunction "55_55") (pintype "input+no_connect"))
    )
    (net (code "201") (name "unconnected-(J36-Pad56)") (class "Default")
      (node (ref "J36") (pin "56") (pinfunction "56_56") (pintype "input+no_connect"))
    )
    (net (code "202") (name "unconnected-(J36-Pad57)") (class "Default")
      (node (ref "J36") (pin "57") (pinfunction "57_57") (pintype "input+no_connect"))
    )
    (net (code "203") (name "unconnected-(J36-Pad58)") (class "Default")
      (node (ref "J36") (pin "58") (pinfunction "58_58") (pintype "input+no_connect"))
    )
    (net (code "204") (name "unconnected-(J36-Pad61)") (class "Default")
      (node (ref "J36") (pin "61") (pinfunction "61_61") (pintype "input+no_connect"))
    )
    (net (code "205") (name "unconnected-(J36-Pad62)") (class "Default")
      (node (ref "J36") (pin "62") (pinfunction "62_62") (pintype "input+no_connect"))
    )
    (net (code "206") (name "unconnected-(J36-Pad63)") (class "Default")
      (node (ref "J36") (pin "63") (pinfunction "63_63") (pintype "input+no_connect"))
    )
    (net (code "207") (name "unconnected-(J36-Pad64)") (class "Default")
      (node (ref "J36") (pin "64") (pinfunction "64_64") (pintype "input+no_connect"))
    )
    (net (code "208") (name "unconnected-(J36-Pad65)") (class "Default")
      (node (ref "J36") (pin "65") (pinfunction "65_65") (pintype "input+no_connect"))
    )
    (net (code "209") (name "unconnected-(J36-Pad66)") (class "Default")
      (node (ref "J36") (pin "66") (pinfunction "66_66") (pintype "input+no_connect"))
    )
    (net (code "210") (name "unconnected-(J36-Pad67)") (class "Default")
      (node (ref "J36") (pin "67") (pinfunction "67_67") (pintype "input+no_connect"))
    )
    (net (code "211") (name "unconnected-(J36-Pad68)") (class "Default")
      (node (ref "J36") (pin "68") (pinfunction "68_68") (pintype "input+no_connect"))
    )
    (net (code "212") (name "unconnected-(J36-Pad71)") (class "Default")
      (node (ref "J36") (pin "71") (pinfunction "71_71") (pintype "input+no_connect"))
    )
    (net (code "213") (name "unconnected-(J36-Pad72)") (class "Default")
      (node (ref "J36") (pin "72") (pinfunction "72_72") (pintype "input+no_connect"))
    )
    (net (code "214") (name "unconnected-(J36-Pad73)") (class "Default")
      (node (ref "J36") (pin "73") (pinfunction "73_73") (pintype "input+no_connect"))
    )
    (net (code "215") (name "unconnected-(J36-Pad74)") (class "Default")
      (node (ref "J36") (pin "74") (pinfunction "74_74") (pintype "input+no_connect"))
    )
    (net (code "216") (name "unconnected-(J36-Pad75)") (class "Default")
      (node (ref "J36") (pin "75") (pinfunction "75_75") (pintype "input+no_connect"))
    )
    (net (code "217") (name "unconnected-(J36-Pad76)") (class "Default")
      (node (ref "J36") (pin "76") (pinfunction "76_76") (pintype "input+no_connect"))
    )
    (net (code "218") (name "unconnected-(J36-Pad81)") (class "Default")
      (node (ref "J36") (pin "81") (pinfunction "81_81") (pintype "input+no_connect"))
    )
    (net (code "219") (name "unconnected-(J36-Pad82)") (class "Default")
      (node (ref "J36") (pin "82") (pinfunction "82_82") (pintype "input+no_connect"))
    )
    (net (code "220") (name "unconnected-(J36-Pad83)") (class "Default")
      (node (ref "J36") (pin "83") (pinfunction "83_83") (pintype "input+no_connect"))
    )
    (net (code "221") (name "unconnected-(J36-Pad84)") (class "Default")
      (node (ref "J36") (pin "84") (pinfunction "84_84") (pintype "input+no_connect"))
    )
    (net (code "222") (name "unconnected-(J37-Pad1)") (class "Default")
      (node (ref "J37") (pin "1") (pinfunction "1_1") (pintype "input+no_connect"))
    )
    (net (code "223") (name "unconnected-(J37-Pad2)") (class "Default")
      (node (ref "J37") (pin "2") (pinfunction "2_2") (pintype "input+no_connect"))
    )
    (net (code "224") (name "unconnected-(J37-Pad3)") (class "Default")
      (node (ref "J37") (pin "3") (pinfunction "3_3") (pintype "input+no_connect"))
    )
    (net (code "225") (name "unconnected-(J37-Pad4)") (class "Default")
      (node (ref "J37") (pin "4") (pinfunction "4_4") (pintype "input+no_connect"))
    )
    (net (code "226") (name "unconnected-(J37-Pad5)") (class "Default")
      (node (ref "J37") (pin "5") (pinfunction "5_5") (pintype "input+no_connect"))
    )
    (net (code "227") (name "unconnected-(J37-Pad6)") (class "Default")
      (node (ref "J37") (pin "6") (pinfunction "6_6") (pintype "input+no_connect"))
    )
    (net (code "228") (name "unconnected-(J37-Pad7)") (class "Default")
      (node (ref "J37") (pin "7") (pinfunction "7_7") (pintype "input+no_connect"))
    )
    (net (code "229") (name "unconnected-(J37-Pad8)") (class "Default")
      (node (ref "J37") (pin "8") (pinfunction "8_8") (pintype "input+no_connect"))
    )
    (net (code "230") (name "unconnected-(J37-Pad11)") (class "Default")
      (node (ref "J37") (pin "11") (pinfunction "11_11") (pintype "input+no_connect"))
    )
    (net (code "231") (name "unconnected-(J37-Pad13)") (class "Default")
      (node (ref "J37") (pin "13") (pinfunction "13_13") (pintype "input+no_connect"))
    )
    (net (code "232") (name "unconnected-(J37-Pad16)") (class "Default")
      (node (ref "J37") (pin "16") (pinfunction "16_16") (pintype "input+no_connect"))
    )
    (net (code "233") (name "unconnected-(J37-Pad22)") (class "Default")
      (node (ref "J37") (pin "22") (pinfunction "22_22") (pintype "input+no_connect"))
    )
    (net (code "234") (name "unconnected-(J37-Pad28)") (class "Default")
      (node (ref "J37") (pin "28") (pinfunction "28_28") (pintype "input+no_connect"))
    )
    (net (code "235") (name "unconnected-(J37-Pad34)") (class "Default")
      (node (ref "J37") (pin "34") (pinfunction "34_34") (pintype "input+no_connect"))
    )
    (net (code "236") (name "unconnected-(J37-Pad41)") (class "Default")
      (node (ref "J37") (pin "41") (pinfunction "41_41") (pintype "input+no_connect"))
    )
    (net (code "237") (name "unconnected-(J37-Pad42)") (class "Default")
      (node (ref "J37") (pin "42") (pinfunction "42_42") (pintype "input+no_connect"))
    )
    (net (code "238") (name "unconnected-(J37-Pad43)") (class "Default")
      (node (ref "J37") (pin "43") (pinfunction "43_43") (pintype "input+no_connect"))
    )
    (net (code "239") (name "unconnected-(J37-Pad44)") (class "Default")
      (node (ref "J37") (pin "44") (pinfunction "44_44") (pintype "input+no_connect"))
    )
    (net (code "240") (name "unconnected-(J37-Pad45)") (class "Default")
      (node (ref "J37") (pin "45") (pinfunction "45_45") (pintype "input+no_connect"))
    )
    (net (code "241") (name "unconnected-(J37-Pad46)") (class "Default")
      (node (ref "J37") (pin "46") (pinfunction "46_46") (pintype "input+no_connect"))
    )
    (net (code "242") (name "unconnected-(J37-Pad47)") (class "Default")
      (node (ref "J37") (pin "47") (pinfunction "47_47") (pintype "input+no_connect"))
    )
    (net (code "243") (name "unconnected-(J37-Pad48)") (class "Default")
      (node (ref "J37") (pin "48") (pinfunction "48_48") (pintype "input+no_connect"))
    )
    (net (code "244") (name "unconnected-(J37-Pad51)") (class "Default")
      (node (ref "J37") (pin "51") (pinfunction "51_51") (pintype "input+no_connect"))
    )
    (net (code "245") (name "unconnected-(J37-Pad52)") (class "Default")
      (node (ref "J37") (pin "52") (pinfunction "52_52") (pintype "input+no_connect"))
    )
    (net (code "246") (name "unconnected-(J37-Pad53)") (class "Default")
      (node (ref "J37") (pin "53") (pinfunction "53_53") (pintype "input+no_connect"))
    )
    (net (code "247") (name "unconnected-(J37-Pad54)") (class "Default")
      (node (ref "J37") (pin "54") (pinfunction "54_54") (pintype "input+no_connect"))
    )
    (net (code "248") (name "unconnected-(J37-Pad55)") (class "Default")
      (node (ref "J37") (pin "55") (pinfunction "55_55") (pintype "input+no_connect"))
    )
    (net (code "249") (name "unconnected-(J37-Pad56)") (class "Default")
      (node (ref "J37") (pin "56") (pinfunction "56_56") (pintype "input+no_connect"))
    )
    (net (code "250") (name "unconnected-(J37-Pad57)") (class "Default")
      (node (ref "J37") (pin "57") (pinfunction "57_57") (pintype "input+no_connect"))
    )
    (net (code "251") (name "unconnected-(J37-Pad58)") (class "Default")
      (node (ref "J37") (pin "58") (pinfunction "58_58") (pintype "input+no_connect"))
    )
    (net (code "252") (name "unconnected-(J37-Pad61)") (class "Default")
      (node (ref "J37") (pin "61") (pinfunction "61_61") (pintype "input+no_connect"))
    )
    (net (code "253") (name "unconnected-(J37-Pad62)") (class "Default")
      (node (ref "J37") (pin "62") (pinfunction "62_62") (pintype "input+no_connect"))
    )
    (net (code "254") (name "unconnected-(J37-Pad63)") (class "Default")
      (node (ref "J37") (pin "63") (pinfunction "63_63") (pintype "input+no_connect"))
    )
    (net (code "255") (name "unconnected-(J37-Pad64)") (class "Default")
      (node (ref "J37") (pin "64") (pinfunction "64_64") (pintype "input+no_connect"))
    )
    (net (code "256") (name "unconnected-(J37-Pad65)") (class "Default")
      (node (ref "J37") (pin "65") (pinfunction "65_65") (pintype "input+no_connect"))
    )
    (net (code "257") (name "unconnected-(J37-Pad66)") (class "Default")
      (node (ref "J37") (pin "66") (pinfunction "66_66") (pintype "input+no_connect"))
    )
    (net (code "258") (name "unconnected-(J37-Pad67)") (class "Default")
      (node (ref "J37") (pin "67") (pinfunction "67_67") (pintype "input+no_connect"))
    )
    (net (code "259") (name "unconnected-(J37-Pad68)") (class "Default")
      (node (ref "J37") (pin "68") (pinfunction "68_68") (pintype "input+no_connect"))
    )
    (net (code "260") (name "unconnected-(J37-Pad71)") (class "Default")
      (node (ref "J37") (pin "71") (pinfunction "71_71") (pintype "input+no_connect"))
    )
    (net (code "261") (name "unconnected-(J37-Pad72)") (class "Default")
      (node (ref "J37") (pin "72") (pinfunction "72_72") (pintype "input+no_connect"))
    )
    (net (code "262") (name "unconnected-(J37-Pad73)") (class "Default")
      (node (ref "J37") (pin "73") (pinfunction "73_73") (pintype "input+no_connect"))
    )
    (net (code "263") (name "unconnected-(J37-Pad74)") (class "Default")
      (node (ref "J37") (pin "74") (pinfunction "74_74") (pintype "input+no_connect"))
    )
    (net (code "264") (name "unconnected-(J37-Pad75)") (class "Default")
      (node (ref "J37") (pin "75") (pinfunction "75_75") (pintype "input+no_connect"))
    )
    (net (code "265") (name "unconnected-(J37-Pad76)") (class "Default")
      (node (ref "J37") (pin "76") (pinfunction "76_76") (pintype "input+no_connect"))
    )
    (net (code "266") (name "unconnected-(J37-Pad77)") (class "Default")
      (node (ref "J37") (pin "77") (pinfunction "77_77") (pintype "input+no_connect"))
    )
    (net (code "267") (name "unconnected-(J37-Pad78)") (class "Default")
      (node (ref "J37") (pin "78") (pinfunction "78_78") (pintype "input+no_connect"))
    )
    (net (code "268") (name "unconnected-(J37-Pad79)") (class "Default")
      (node (ref "J37") (pin "79") (pinfunction "79_79") (pintype "input+no_connect"))
    )
    (net (code "269") (name "unconnected-(J37-Pad80)") (class "Default")
      (node (ref "J37") (pin "80") (pinfunction "80_80") (pintype "input+no_connect"))
    )
    (net (code "270") (name "unconnected-(J37-Pad81)") (class "Default")
      (node (ref "J37") (pin "81") (pinfunction "81_81") (pintype "input+no_connect"))
    )
    (net (code "271") (name "unconnected-(J37-Pad82)") (class "Default")
      (node (ref "J37") (pin "82") (pinfunction "82_82") (pintype "input+no_connect"))
    )
    (net (code "272") (name "unconnected-(J37-Pad83)") (class "Default")
      (node (ref "J37") (pin "83") (pinfunction "83_83") (pintype "input+no_connect"))
    )
    (net (code "273") (name "unconnected-(J37-Pad84)") (class "Default")
      (node (ref "J37") (pin "84") (pinfunction "84_84") (pintype "input+no_connect"))
    )
  )
)
